# fl3xwatch.net
KiCad netlist of a schematic drawn in EAGLE
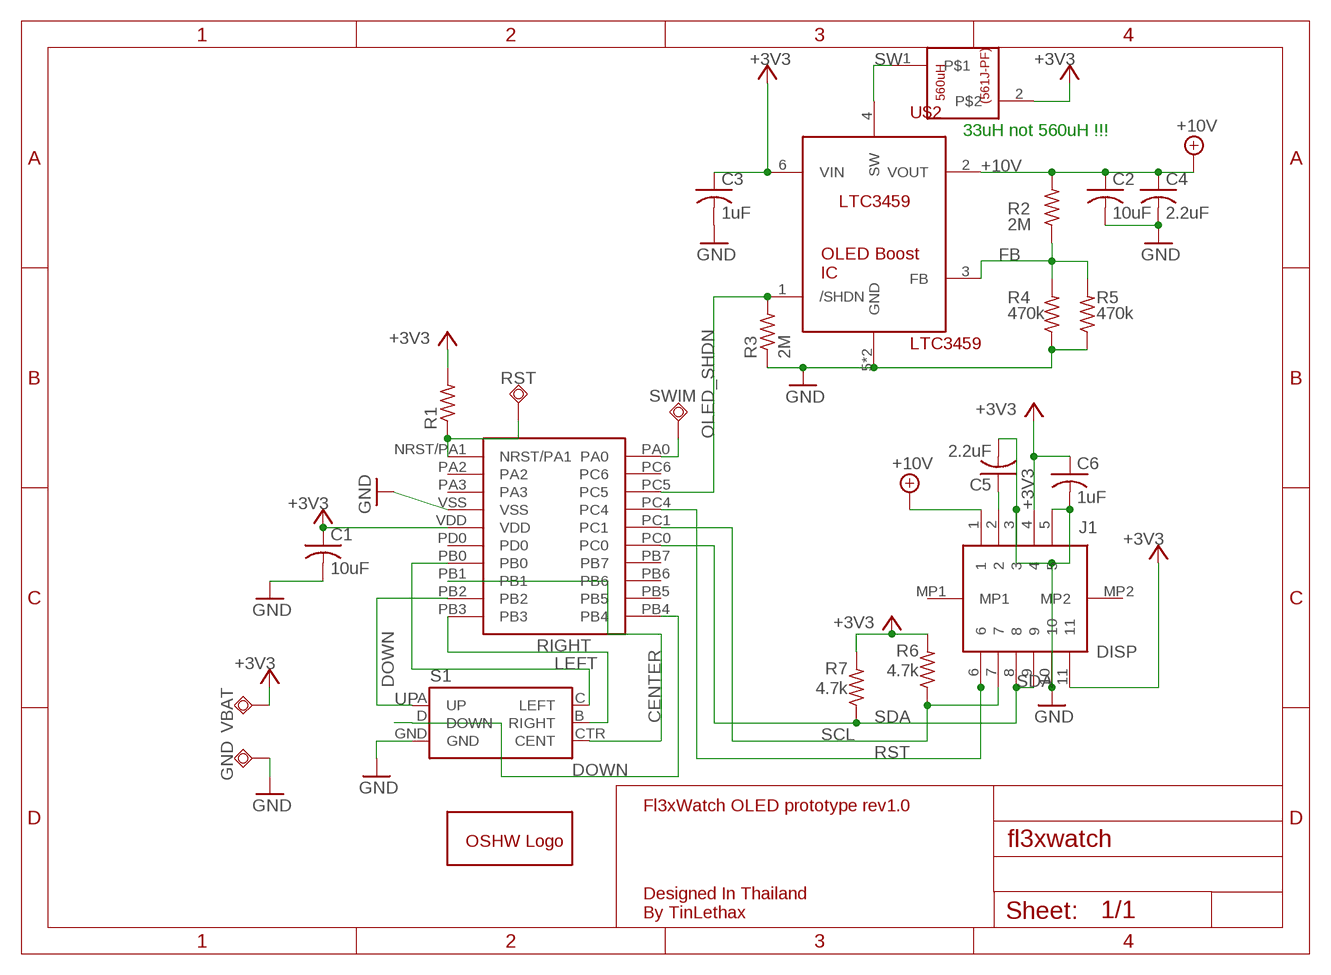
[diagram p0: schematic, sheet 1]

(export (version "E")
  (design (tool "Eeschema 10.0.6"))
  (components
    (comp (ref "C1")
      (value "10uF")
      (footprint "eagle-import:C0805")
      (libsource (lib "eagle-import") (part "C-USC0805"))
    )
    (comp (ref "C2")
      (value "10uF")
      (footprint "eagle-import:C0805")
      (libsource (lib "eagle-import") (part "C-USC0805"))
    )
    (comp (ref "C3")
      (value "1uF")
      (footprint "eagle-import:C0603")
      (libsource (lib "eagle-import") (part "C-USC0603"))
    )
    (comp (ref "C4")
      (value "2.2uF")
      (footprint "eagle-import:C0603")
      (libsource (lib "eagle-import") (part "C-USC0603"))
    )
    (comp (ref "C5")
      (value "2.2uF")
      (footprint "eagle-import:C0603")
      (libsource (lib "eagle-import") (part "C-USC0603"))
    )
    (comp (ref "C6")
      (value "1uF")
      (footprint "eagle-import:C0603")
      (libsource (lib "eagle-import") (part "C-USC0603"))
    )
    (comp (ref "GND")
      (value "TPSQTP20SQ")
      (footprint "eagle-import:TP20SQ")
      (libsource (lib "eagle-import") (part "TPSQTP20SQ"))
    )
    (comp (ref "GOLD_ORB_SM1")
      (value "OSHWLOGOLOGO5MM")
      (footprint "eagle-import:OSHW_5MM")
      (libsource (lib "eagle-import") (part "OSHWLOGOLOGO5MM"))
    )
    (comp (ref "J1")
      (value "DISP")
      (footprint "eagle-import:FH35C11S03SHW50")
      (fields
        (field (name "MANUFACTURER_PART_NUMBER") "FH35C-11S-0.3SHW(50)")
        (field (name "MOUSER_PART_NUMBER") "798-FH35C11S03SHW50")
      )
      (libsource (lib "eagle-import") (part "FH35C-11S-0.3SHW_50_"))
    )
    (comp (ref "L1")
      (value "33uH")
      (footprint "eagle-import:INDC4526X50N")
      (libsource (lib "eagle-import") (part "NL453232T-561J-PF"))
    )
    (comp (ref "R1")
      (value "R-US_R0603")
      (footprint "eagle-import:R0603")
      (libsource (lib "eagle-import") (part "R-US_R0603"))
    )
    (comp (ref "R2")
      (value "2M")
      (footprint "eagle-import:R0603")
      (libsource (lib "eagle-import") (part "R-US_R0603"))
    )
    (comp (ref "R3")
      (value "2M")
      (footprint "eagle-import:R0603")
      (libsource (lib "eagle-import") (part "R-US_R0603"))
    )
    (comp (ref "R4")
      (value "470k")
      (footprint "eagle-import:R0805")
      (libsource (lib "eagle-import") (part "R-US_R0805"))
    )
    (comp (ref "R5")
      (value "470k")
      (footprint "eagle-import:R0805")
      (libsource (lib "eagle-import") (part "R-US_R0805"))
    )
    (comp (ref "R6")
      (value "4.7k")
      (footprint "eagle-import:R0603")
      (libsource (lib "eagle-import") (part "R-US_R0603"))
    )
    (comp (ref "R7")
      (value "4.7k")
      (footprint "eagle-import:R0603")
      (libsource (lib "eagle-import") (part "R-US_R0603"))
    )
    (comp (ref "RST")
      (value "TPSQTP15R")
      (footprint "eagle-import:TP15R")
      (libsource (lib "eagle-import") (part "TPSQTP15R"))
    )
    (comp (ref "S1")
      (value "SPARKFUN-ELECTROMECHANICAL_JOYSTICK_MINI")
      (footprint "eagle-import:SPARKFUN-ELECTROMECHANICAL_JOYSTICK_MINI")
      (libsource (lib "eagle-import") (part "SPARKFUN-ELECTROMECHANICAL_JOYSTICK_MINI"))
    )
    (comp (ref "SWIM")
      (value "TPSQTP15R")
      (footprint "eagle-import:TP15R")
      (libsource (lib "eagle-import") (part "TPSQTP15R"))
    )
    (comp (ref "U$1")
      (value "STM8L151F3")
      (footprint "eagle-import:UFQFPN-20")
      (libsource (lib "eagle-import") (part "STM8L151F3"))
    )
    (comp (ref "U$2")
      (value "LTC3459")
      (footprint "eagle-import:SON50P300X200X75-7T165X135N")
      (libsource (lib "eagle-import") (part "LTC3459"))
    )
    (comp (ref "VBAT")
      (value "TPSQTP20SQ")
      (footprint "eagle-import:TP20SQ")
      (libsource (lib "eagle-import") (part "TPSQTP20SQ"))
    )
  )
  (nets
    (net (code "1") (name "+3V3") (class "Default")
      (node (ref "C1") (pin "1") (pinfunction "1_1") (pintype "passive"))
      (node (ref "C3") (pin "1") (pinfunction "1_1") (pintype "passive"))
      (node (ref "C6") (pin "1") (pinfunction "1_1") (pintype "passive"))
      (node (ref "J1") (pin "11") (pinfunction "11_11") (pintype "bidirectional"))
      (node (ref "J1") (pin "4") (pinfunction "4_4") (pintype "bidirectional"))
      (node (ref "L1") (pin "2") (pinfunction "P$2_2") (pintype "bidirectional"))
      (node (ref "R1") (pin "2") (pinfunction "2_2") (pintype "passive"))
      (node (ref "R6") (pin "2") (pinfunction "2_2") (pintype "passive"))
      (node (ref "R7") (pin "2") (pinfunction "2_2") (pintype "passive"))
      (node (ref "U$1") (pin "VDD") (pinfunction "VDD_VDD") (pintype "bidirectional"))
      (node (ref "U$2") (pin "6") (pinfunction "VIN_6") (pintype "bidirectional"))
      (node (ref "VBAT") (pin "TP") (pinfunction "TP_TP") (pintype "input"))
    )
    (net (code "2") (name "+10V") (class "Default")
      (node (ref "C2") (pin "1") (pinfunction "1_1") (pintype "passive"))
      (node (ref "C4") (pin "1") (pinfunction "1_1") (pintype "passive"))
      (node (ref "J1") (pin "1") (pinfunction "1_1") (pintype "bidirectional"))
      (node (ref "R2") (pin "2") (pinfunction "2_2") (pintype "passive"))
      (node (ref "U$2") (pin "2") (pinfunction "VOUT_2") (pintype "bidirectional"))
    )
    (net (code "3") (name "/CENTER") (class "Default")
      (node (ref "S1") (pin "CTR") (pinfunction "CENT_CTR") (pintype "bidirectional"))
      (node (ref "U$1") (pin "PB1") (pinfunction "PB1_PB1") (pintype "bidirectional"))
    )
    (net (code "4") (name "/DOWN") (class "Default")
      (node (ref "S1") (pin "D") (pinfunction "DOWN_D") (pintype "bidirectional"))
      (node (ref "U$1") (pin "PB4") (pinfunction "PB4_PB4") (pintype "bidirectional"))
    )
    (net (code "5") (name "/FB") (class "Default")
      (node (ref "R2") (pin "1") (pinfunction "1_1") (pintype "passive"))
      (node (ref "R4") (pin "2") (pinfunction "2_2") (pintype "passive"))
      (node (ref "R5") (pin "2") (pinfunction "2_2") (pintype "passive"))
      (node (ref "U$2") (pin "3") (pinfunction "FB_3") (pintype "bidirectional"))
    )
    (net (code "6") (name "/LEFT") (class "Default")
      (node (ref "S1") (pin "C") (pinfunction "LEFT_C") (pintype "bidirectional"))
      (node (ref "U$1") (pin "PB0") (pinfunction "PB0_PB0") (pintype "bidirectional"))
    )
    (net (code "7") (name "/OLED_SHDN") (class "Default")
      (node (ref "R3") (pin "2") (pinfunction "2_2") (pintype "passive"))
      (node (ref "U$1") (pin "PC5") (pinfunction "PC5_PC5") (pintype "bidirectional"))
      (node (ref "U$2") (pin "1") (pinfunction "/SHDN_1") (pintype "bidirectional"))
    )
    (net (code "8") (name "/RIGHT") (class "Default")
      (node (ref "S1") (pin "B") (pinfunction "RIGHT_B") (pintype "bidirectional"))
      (node (ref "U$1") (pin "PB3") (pinfunction "PB3_PB3") (pintype "bidirectional"))
    )
    (net (code "9") (name "/RST") (class "Default")
      (node (ref "J1") (pin "6") (pinfunction "6_6") (pintype "bidirectional"))
      (node (ref "U$1") (pin "PC4") (pinfunction "PC4_PC4") (pintype "bidirectional"))
    )
    (net (code "10") (name "/SCL") (class "Default")
      (node (ref "J1") (pin "7") (pinfunction "7_7") (pintype "bidirectional"))
      (node (ref "R6") (pin "1") (pinfunction "1_1") (pintype "passive"))
      (node (ref "U$1") (pin "PC1") (pinfunction "PC1_PC1") (pintype "bidirectional"))
    )
    (net (code "11") (name "/SDA") (class "Default")
      (node (ref "J1") (pin "8") (pinfunction "8_8") (pintype "bidirectional"))
      (node (ref "J1") (pin "9") (pinfunction "9_9") (pintype "bidirectional"))
      (node (ref "R7") (pin "1") (pinfunction "1_1") (pintype "passive"))
      (node (ref "U$1") (pin "PC0") (pinfunction "PC0_PC0") (pintype "bidirectional"))
    )
    (net (code "12") (name "/SW") (class "Default")
      (node (ref "L1") (pin "1") (pinfunction "P$1_1") (pintype "bidirectional"))
      (node (ref "U$2") (pin "4") (pinfunction "SW_4") (pintype "bidirectional"))
    )
    (net (code "13") (name "/UP") (class "Default")
      (node (ref "S1") (pin "A") (pinfunction "UP_A") (pintype "bidirectional"))
      (node (ref "U$1") (pin "PB2") (pinfunction "PB2_PB2") (pintype "bidirectional"))
    )
    (net (code "14") (name "GND") (class "Default")
      (node (ref "C1") (pin "2") (pinfunction "2_2") (pintype "passive"))
      (node (ref "C2") (pin "2") (pinfunction "2_2") (pintype "passive"))
      (node (ref "C3") (pin "2") (pinfunction "2_2") (pintype "passive"))
      (node (ref "C4") (pin "2") (pinfunction "2_2") (pintype "passive"))
      (node (ref "C5") (pin "2") (pinfunction "2_2") (pintype "passive"))
      (node (ref "C6") (pin "2") (pinfunction "2_2") (pintype "passive"))
      (node (ref "GND") (pin "TP") (pinfunction "TP_TP") (pintype "input"))
      (node (ref "J1") (pin "10") (pinfunction "10_10") (pintype "bidirectional"))
      (node (ref "J1") (pin "3") (pinfunction "3_3") (pintype "bidirectional"))
      (node (ref "J1") (pin "5") (pinfunction "5_5") (pintype "bidirectional"))
      (node (ref "R3") (pin "1") (pinfunction "1_1") (pintype "passive"))
      (node (ref "R4") (pin "1") (pinfunction "1_1") (pintype "passive"))
      (node (ref "R5") (pin "1") (pinfunction "1_1") (pintype "passive"))
      (node (ref "S1") (pin "GND") (pinfunction "GND_GND") (pintype "bidirectional"))
      (node (ref "U$1") (pin "VSS") (pinfunction "VSS_VSS") (pintype "bidirectional"))
      (node (ref "U$2") (pin "5") (pinfunction "GND_5") (pintype "bidirectional"))
      (node (ref "U$2") (pin "7") (pinfunction "GND_7") (pintype "bidirectional"))
    )
    (net (code "15") (name "Net-(C5-Pad1)") (class "Default")
      (node (ref "C5") (pin "1") (pinfunction "1_1") (pintype "passive"))
      (node (ref "J1") (pin "2") (pinfunction "2_2") (pintype "bidirectional"))
    )
    (net (code "16") (name "Net-(R1-Pad1)") (class "Default")
      (node (ref "R1") (pin "1") (pinfunction "1_1") (pintype "passive"))
      (node (ref "RST") (pin "TP") (pinfunction "TP_TP") (pintype "input"))
      (node (ref "U$1") (pin "NRST/PA1") (pinfunction "NRST/PA1_NRST/PA1") (pintype "bidirectional"))
    )
    (net (code "17") (name "Net-(SWIM-PadTP)") (class "Default")
      (node (ref "SWIM") (pin "TP") (pinfunction "TP_TP") (pintype "input"))
      (node (ref "U$1") (pin "PA0") (pinfunction "PA0_PA0") (pintype "bidirectional"))
    )
    (net (code "18") (name "unconnected-(J1-PadMP1)") (class "Default")
      (node (ref "J1") (pin "MP1") (pinfunction "MP1_MP1") (pintype "bidirectional"))
    )
    (net (code "19") (name "unconnected-(J1-PadMP2)") (class "Default")
      (node (ref "J1") (pin "MP2") (pinfunction "MP2_MP2") (pintype "bidirectional"))
    )
    (net (code "20") (name "unconnected-(U$1-PadPA2)") (class "Default")
      (node (ref "U$1") (pin "PA2") (pinfunction "PA2_PA2") (pintype "bidirectional"))
    )
    (net (code "21") (name "unconnected-(U$1-PadPA3)") (class "Default")
      (node (ref "U$1") (pin "PA3") (pinfunction "PA3_PA3") (pintype "bidirectional"))
    )
    (net (code "22") (name "unconnected-(U$1-PadPB5)") (class "Default")
      (node (ref "U$1") (pin "PB5") (pinfunction "PB5_PB5") (pintype "bidirectional"))
    )
    (net (code "23") (name "unconnected-(U$1-PadPB6)") (class "Default")
      (node (ref "U$1") (pin "PB6") (pinfunction "PB6_PB6") (pintype "bidirectional"))
    )
    (net (code "24") (name "unconnected-(U$1-PadPB7)") (class "Default")
      (node (ref "U$1") (pin "PB7") (pinfunction "PB7_PB7") (pintype "bidirectional"))
    )
    (net (code "25") (name "unconnected-(U$1-PadPC6)") (class "Default")
      (node (ref "U$1") (pin "PC6") (pinfunction "PC6_PC6") (pintype "bidirectional"))
    )
    (net (code "26") (name "unconnected-(U$1-PadPD0)") (class "Default")
      (node (ref "U$1") (pin "PD0") (pinfunction "PD0_PD0") (pintype "bidirectional"))
    )
  )
)
